# ATmega128RFA1-DevBoard.net
KiCad netlist of a schematic drawn in EAGLE
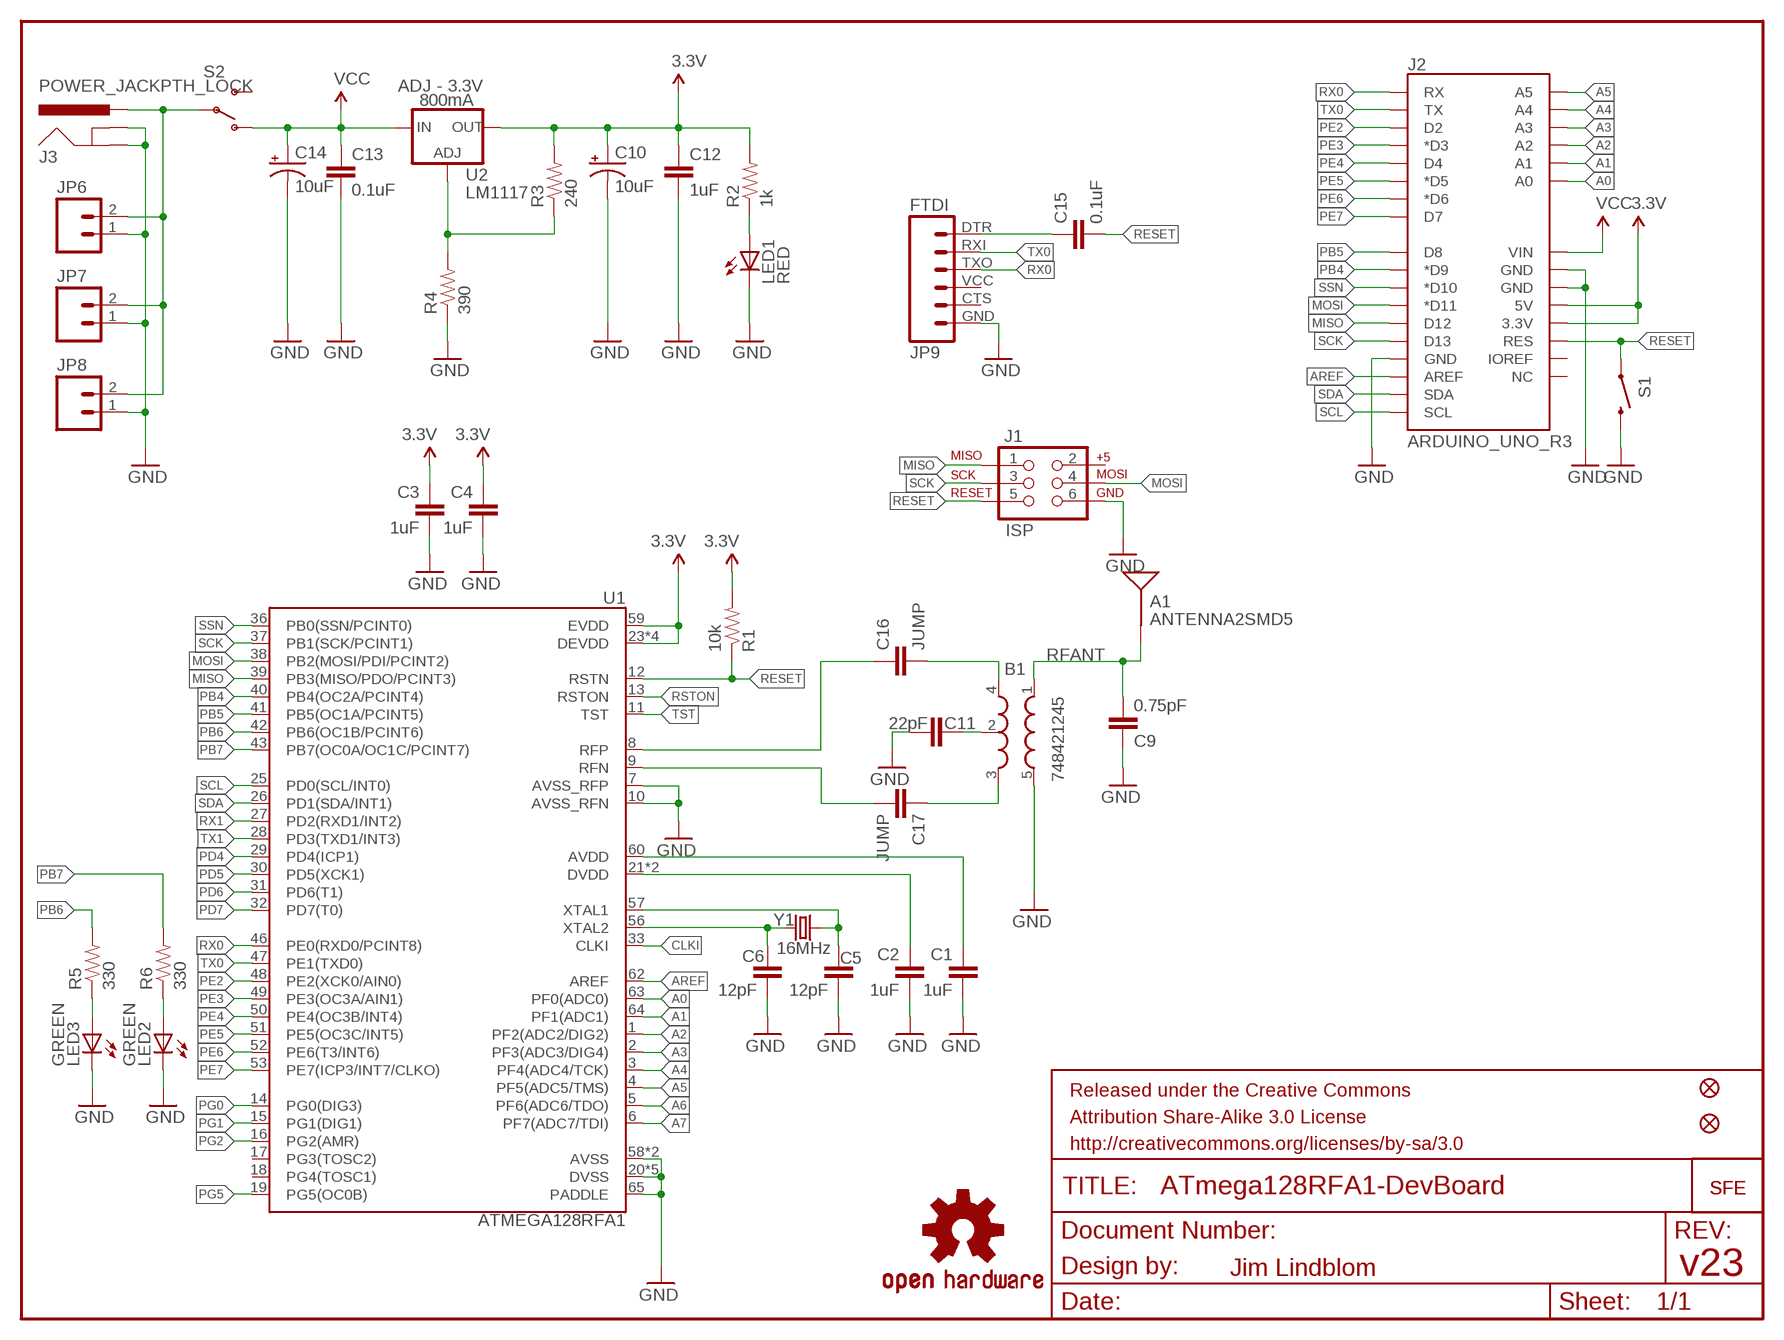
[diagram p0: schematic, sheet 1]

(export (version "E")
  (design (tool "Eeschema 10.0.6"))
  (components
    (comp (ref "A1")
      (value "ANTENNA2SMD5")
      (footprint "eagle-import:ANTENNA-CHIP5")
      (libsource (lib "eagle-import") (part "ANTENNA2SMD5"))
    )
    (comp (ref "B1")
      (value "748421245")
      (footprint "eagle-import:BALUN")
      (libsource (lib "eagle-import") (part "BALUN0805"))
    )
    (comp (ref "C1")
      (value "1uF")
      (footprint "eagle-import:0402-CAP")
      (libsource (lib "eagle-import") (part "SparkFun-Passives_CAP0402-CAP"))
    )
    (comp (ref "C2")
      (value "1uF")
      (footprint "eagle-import:0402-CAP")
      (libsource (lib "eagle-import") (part "SparkFun-Passives_CAP0402-CAP"))
    )
    (comp (ref "C3")
      (value "1uF")
      (footprint "eagle-import:0402-CAP")
      (libsource (lib "eagle-import") (part "SparkFun-Passives_CAP0402-CAP"))
    )
    (comp (ref "C4")
      (value "1uF")
      (footprint "eagle-import:0402-CAP")
      (libsource (lib "eagle-import") (part "SparkFun-Passives_CAP0402-CAP"))
    )
    (comp (ref "C5")
      (value "12pF")
      (footprint "eagle-import:0402-CAP")
      (libsource (lib "eagle-import") (part "SparkFun-Passives_CAP0402-CAP"))
    )
    (comp (ref "C6")
      (value "12pF")
      (footprint "eagle-import:0402-CAP")
      (libsource (lib "eagle-import") (part "SparkFun-Passives_CAP0402-CAP"))
    )
    (comp (ref "C9")
      (value "0.75pF")
      (footprint "eagle-import:0402-CAP")
      (libsource (lib "eagle-import") (part "SparkFun-Passives_CAP0402-CAP"))
    )
    (comp (ref "C10")
      (value "10uF")
      (footprint "eagle-import:EIA3216")
      (libsource (lib "eagle-import") (part "CAP_POL1206"))
    )
    (comp (ref "C11")
      (value "22pF")
      (footprint "eagle-import:0402-CAP")
      (libsource (lib "eagle-import") (part "SparkFun-Passives_CAP0402-CAP"))
    )
    (comp (ref "C12")
      (value "1uF")
      (footprint "eagle-import:0402-CAP")
      (libsource (lib "eagle-import") (part "SparkFun-Passives_CAP0402-CAP"))
    )
    (comp (ref "C13")
      (value "0.1uF")
      (footprint "eagle-import:0402-CAP")
      (libsource (lib "eagle-import") (part "SparkFun-Passives_CAP0402-CAP"))
    )
    (comp (ref "C14")
      (value "10uF")
      (footprint "eagle-import:EIA3216")
      (libsource (lib "eagle-import") (part "CAP_POL1206"))
    )
    (comp (ref "C15")
      (value "0.1uF")
      (footprint "eagle-import:0402-CAP")
      (libsource (lib "eagle-import") (part "SparkFun-Passives_CAP0402-CAP"))
    )
    (comp (ref "C16")
      (value "JUMP")
      (footprint "eagle-import:0402-CAP")
      (libsource (lib "eagle-import") (part "CAP0402-CAP"))
    )
    (comp (ref "C17")
      (value "JUMP")
      (footprint "eagle-import:0402-CAP")
      (libsource (lib "eagle-import") (part "CAP0402-CAP"))
    )
    (comp (ref "FID1")
      (value "FIDUCIALUFIDUCIAL")
      (footprint "eagle-import:MICRO-FIDUCIAL")
      (libsource (lib "eagle-import") (part "FIDUCIALUFIDUCIAL"))
    )
    (comp (ref "FID2")
      (value "FIDUCIALUFIDUCIAL")
      (footprint "eagle-import:MICRO-FIDUCIAL")
      (libsource (lib "eagle-import") (part "FIDUCIALUFIDUCIAL"))
    )
    (comp (ref "J1")
      (value "ISP")
      (footprint "eagle-import:2X3-NS")
      (libsource (lib "eagle-import") (part "AVR_SPI_PRG_6NS"))
    )
    (comp (ref "J2")
      (value "ARDUINO_UNO_R3")
      (footprint "eagle-import:ARDUINO_UNO_R3")
      (libsource (lib "eagle-import") (part "ARDUINO_UNO_R3"))
    )
    (comp (ref "J3")
      (value "POWER_JACKPTH_LOCK")
      (footprint "eagle-import:POWER_JACK_PTH_LOCK")
      (libsource (lib "eagle-import") (part "POWER_JACKPTH_LOCK"))
    )
    (comp (ref "JP4")
      (value "LOGO-SFENEW")
      (footprint "eagle-import:SFE-NEW-WEBLOGO")
      (libsource (lib "eagle-import") (part "LOGO-SFENEW"))
    )
    (comp (ref "JP6")
      (value "M02JST-PTH-2")
      (footprint "eagle-import:JST-2-PTH")
      (libsource (lib "eagle-import") (part "M02JST-PTH-2"))
    )
    (comp (ref "JP7")
      (value "M021X02_NO_SILK")
      (footprint "eagle-import:1X02_NO_SILK")
      (libsource (lib "eagle-import") (part "M021X02_NO_SILK"))
    )
    (comp (ref "JP8")
      (value "M023.5MM-NO_SILK")
      (footprint "eagle-import:SCREWTERMINAL-3.5MM-2-NS")
      (libsource (lib "eagle-import") (part "M023.5MM-NO_SILK"))
    )
    (comp (ref "JP9")
      (value "FTDI")
      (footprint "eagle-import:FTDI_BASIC")
      (libsource (lib "eagle-import") (part "FTDI_BASICPTH"))
    )
    (comp (ref "JP10")
      (value "LOGO-SFENEW")
      (footprint "eagle-import:SFE-NEW-WEBLOGO")
      (libsource (lib "eagle-import") (part "LOGO-SFENEW"))
    )
    (comp (ref "LED1")
      (value "RED")
      (footprint "eagle-import:LED-0603")
      (libsource (lib "eagle-import") (part "LED0603"))
    )
    (comp (ref "LED2")
      (value "GREEN")
      (footprint "eagle-import:LED-0603")
      (libsource (lib "eagle-import") (part "LED0603"))
    )
    (comp (ref "LED3")
      (value "GREEN")
      (footprint "eagle-import:LED-0603")
      (libsource (lib "eagle-import") (part "LED0603"))
    )
    (comp (ref "R1")
      (value "10k")
      (footprint "eagle-import:0402-RES")
      (libsource (lib "eagle-import") (part "SparkFun-Passives_RESISTOR0402-RES"))
    )
    (comp (ref "R2")
      (value "1k")
      (footprint "eagle-import:0402-RES")
      (libsource (lib "eagle-import") (part "SparkFun-Passives_RESISTOR0402-RES"))
    )
    (comp (ref "R3")
      (value "240")
      (footprint "eagle-import:0402-RES")
      (libsource (lib "eagle-import") (part "RESISTOR0402-RES"))
    )
    (comp (ref "R4")
      (value "390")
      (footprint "eagle-import:0402-RES")
      (libsource (lib "eagle-import") (part "RESISTOR0402-RES"))
    )
    (comp (ref "R5")
      (value "330")
      (footprint "eagle-import:0402-RES")
      (libsource (lib "eagle-import") (part "RESISTOR0402-RES"))
    )
    (comp (ref "R6")
      (value "330")
      (footprint "eagle-import:0402-RES")
      (libsource (lib "eagle-import") (part "RESISTOR0402-RES"))
    )
    (comp (ref "S1")
      (value "SWITCH-MOMENTARY-2SMD")
      (footprint "eagle-import:TACTILE_SWITCH_SMD")
      (libsource (lib "eagle-import") (part "SWITCH-MOMENTARY-2SMD"))
    )
    (comp (ref "S2")
      (value "SWITCH-SPST-SMD-A")
      (footprint "eagle-import:SWITCH-SPST-SMD-A")
      (libsource (lib "eagle-import") (part "SWITCH-SPST-SMD-A"))
    )
    (comp (ref "U$1")
      (value "OSHW-LOGOS")
      (footprint "eagle-import:OSHW-LOGO-S")
      (libsource (lib "eagle-import") (part "OSHW-LOGOS"))
    )
    (comp (ref "U1")
      (value "ATMEGA128RFA1")
      (footprint "eagle-import:QFN-64")
      (libsource (lib "eagle-import") (part "ATMEGA128RFA1"))
    )
    (comp (ref "U2")
      (value "LM1117")
      (footprint "eagle-import:SOT223")
      (libsource (lib "eagle-import") (part "V_REG_317SMD"))
    )
    (comp (ref "Y1")
      (value "16MHz")
      (footprint "eagle-import:CRYSTAL-SMD-5X3")
      (libsource (lib "eagle-import") (part "CRYSTAL5X3"))
    )
  )
  (nets
    (net (code "1") (name "/RFANT") (class "Default")
      (node (ref "A1") (pin "FEED") (pinfunction "SIGNAL_FEED") (pintype "bidirectional"))
      (node (ref "B1") (pin "1") (pinfunction "IN_1") (pintype "bidirectional"))
      (node (ref "C9") (pin "2") (pinfunction "2_2") (pintype "passive"))
    )
    (net (code "2") (name "3.3V") (class "Default")
      (node (ref "C10") (pin "A") (pinfunction "+_A") (pintype "passive"))
      (node (ref "C12") (pin "1") (pinfunction "1_1") (pintype "passive"))
      (node (ref "C3") (pin "1") (pinfunction "1_1") (pintype "passive"))
      (node (ref "C4") (pin "1") (pinfunction "1_1") (pintype "passive"))
      (node (ref "J2") (pin "3.3V") (pinfunction "3.3V_3.3V") (pintype "bidirectional"))
      (node (ref "J2") (pin "5V") (pinfunction "5V_5V") (pintype "bidirectional"))
      (node (ref "R1") (pin "2") (pinfunction "2_2") (pintype "passive"))
      (node (ref "R2") (pin "2") (pinfunction "2_2") (pintype "passive"))
      (node (ref "R3") (pin "2") (pinfunction "2_2") (pintype "passive"))
      (node (ref "U1") (pin "23") (pinfunction "DEVDD_23") (pintype "bidirectional"))
      (node (ref "U1") (pin "34") (pinfunction "DEVDD_34") (pintype "bidirectional"))
      (node (ref "U1") (pin "44") (pinfunction "DEVDD_44") (pintype "bidirectional"))
      (node (ref "U1") (pin "54") (pinfunction "DEVDD_54") (pintype "bidirectional"))
      (node (ref "U1") (pin "59") (pinfunction "EVDD_59") (pintype "bidirectional"))
      (node (ref "U2") (pin "2") (pinfunction "OUT_2") (pintype "output"))
    )
    (net (code "3") (name "A0") (class "Default")
      (node (ref "J2") (pin "A0") (pinfunction "A0_A0") (pintype "bidirectional"))
      (node (ref "U1") (pin "63") (pinfunction "PF0(ADC0)_63") (pintype "bidirectional"))
    )
    (net (code "4") (name "A1") (class "Default")
      (node (ref "J2") (pin "A1") (pinfunction "A1_A1") (pintype "bidirectional"))
      (node (ref "U1") (pin "64") (pinfunction "PF1(ADC1)_64") (pintype "bidirectional"))
    )
    (net (code "5") (name "A2") (class "Default")
      (node (ref "J2") (pin "A2") (pinfunction "A2_A2") (pintype "bidirectional"))
      (node (ref "U1") (pin "1") (pinfunction "PF2(ADC2/DIG2)_1") (pintype "bidirectional"))
    )
    (net (code "6") (name "A3") (class "Default")
      (node (ref "J2") (pin "A3") (pinfunction "A3_A3") (pintype "bidirectional"))
      (node (ref "U1") (pin "2") (pinfunction "PF3(ADC3/DIG4)_2") (pintype "bidirectional"))
    )
    (net (code "7") (name "A4") (class "Default")
      (node (ref "J2") (pin "A4") (pinfunction "A4_A4") (pintype "bidirectional"))
      (node (ref "U1") (pin "3") (pinfunction "PF4(ADC4/TCK)_3") (pintype "bidirectional"))
    )
    (net (code "8") (name "A5") (class "Default")
      (node (ref "J2") (pin "A5") (pinfunction "A5_A5") (pintype "bidirectional"))
      (node (ref "U1") (pin "4") (pinfunction "PF5(ADC5/TMS)_4") (pintype "bidirectional"))
    )
    (net (code "9") (name "A6") (class "Default")
      (node (ref "U1") (pin "5") (pinfunction "PF6(ADC6/TDO)_5") (pintype "bidirectional"))
    )
    (net (code "10") (name "A7") (class "Default")
      (node (ref "U1") (pin "6") (pinfunction "PF7(ADC7/TDI)_6") (pintype "bidirectional"))
    )
    (net (code "11") (name "AREF") (class "Default")
      (node (ref "J2") (pin "AREF") (pinfunction "AREF_AREF") (pintype "bidirectional"))
      (node (ref "U1") (pin "62") (pinfunction "AREF_62") (pintype "bidirectional"))
    )
    (net (code "12") (name "CLKI") (class "Default")
      (node (ref "U1") (pin "33") (pinfunction "CLKI_33") (pintype "bidirectional"))
    )
    (net (code "13") (name "GND") (class "Default")
      (node (ref "B1") (pin "5") (pinfunction "GND_5") (pintype "bidirectional"))
      (node (ref "C1") (pin "2") (pinfunction "2_2") (pintype "passive"))
      (node (ref "C10") (pin "C") (pinfunction "-_C") (pintype "passive"))
      (node (ref "C11") (pin "2") (pinfunction "2_2") (pintype "passive"))
      (node (ref "C12") (pin "2") (pinfunction "2_2") (pintype "passive"))
      (node (ref "C13") (pin "2") (pinfunction "2_2") (pintype "passive"))
      (node (ref "C14") (pin "C") (pinfunction "-_C") (pintype "passive"))
      (node (ref "C2") (pin "2") (pinfunction "2_2") (pintype "passive"))
      (node (ref "C3") (pin "2") (pinfunction "2_2") (pintype "passive"))
      (node (ref "C4") (pin "2") (pinfunction "2_2") (pintype "passive"))
      (node (ref "C5") (pin "2") (pinfunction "2_2") (pintype "passive"))
      (node (ref "C6") (pin "2") (pinfunction "2_2") (pintype "passive"))
      (node (ref "C9") (pin "1") (pinfunction "1_1") (pintype "passive"))
      (node (ref "J1") (pin "6") (pinfunction "6_6") (pintype "passive"))
      (node (ref "J2") (pin "GND@0") (pinfunction "GND_GND@0") (pintype "bidirectional"))
      (node (ref "J2") (pin "GND@1") (pinfunction "GND_GND@1") (pintype "bidirectional"))
      (node (ref "J2") (pin "GND@2") (pinfunction "GND_GND@2") (pintype "bidirectional"))
      (node (ref "J3") (pin "GND") (pinfunction "GND_GND") (pintype "bidirectional"))
      (node (ref "J3") (pin "GNDBREAK") (pinfunction "GNDBREAK_GNDBREAK") (pintype "bidirectional"))
      (node (ref "JP6") (pin "1") (pinfunction "1_1") (pintype "passive"))
      (node (ref "JP7") (pin "1") (pinfunction "1_1") (pintype "passive"))
      (node (ref "JP8") (pin "1") (pinfunction "1_1") (pintype "passive"))
      (node (ref "JP9") (pin "GND") (pinfunction "6_GND") (pintype "passive"))
      (node (ref "LED1") (pin "C") (pinfunction "C_C") (pintype "passive"))
      (node (ref "LED2") (pin "C") (pinfunction "C_C") (pintype "passive"))
      (node (ref "LED3") (pin "C") (pinfunction "C_C") (pintype "passive"))
      (node (ref "R4") (pin "1") (pinfunction "1_1") (pintype "passive"))
      (node (ref "S1") (pin "3") (pinfunction "2_3") (pintype "passive"))
      (node (ref "U1") (pin "10") (pinfunction "AVSS_RFN_10") (pintype "bidirectional"))
      (node (ref "U1") (pin "20") (pinfunction "DVSS_20") (pintype "bidirectional"))
      (node (ref "U1") (pin "24") (pinfunction "DVSS_24") (pintype "bidirectional"))
      (node (ref "U1") (pin "35") (pinfunction "DVSS_35") (pintype "bidirectional"))
      (node (ref "U1") (pin "45") (pinfunction "DVSS_45") (pintype "bidirectional"))
      (node (ref "U1") (pin "55") (pinfunction "DVSS_55") (pintype "bidirectional"))
      (node (ref "U1") (pin "58") (pinfunction "AVSS_58") (pintype "bidirectional"))
      (node (ref "U1") (pin "61") (pinfunction "AVSS_61") (pintype "bidirectional"))
      (node (ref "U1") (pin "65") (pinfunction "PADDLE_65") (pintype "bidirectional"))
      (node (ref "U1") (pin "7") (pinfunction "AVSS_RFP_7") (pintype "bidirectional"))
    )
    (net (code "14") (name "MISO") (class "Default")
      (node (ref "J1") (pin "1") (pinfunction "1_1") (pintype "passive"))
      (node (ref "J2") (pin "D12") (pinfunction "D12_D12") (pintype "bidirectional"))
      (node (ref "U1") (pin "39") (pinfunction "PB3(MISO/PDO/PCINT3)_39") (pintype "bidirectional"))
    )
    (net (code "15") (name "MOSI") (class "Default")
      (node (ref "J1") (pin "4") (pinfunction "4_4") (pintype "passive"))
      (node (ref "J2") (pin "D11") (pinfunction "*D11_D11") (pintype "bidirectional"))
      (node (ref "U1") (pin "38") (pinfunction "PB2(MOSI/PDI/PCINT2)_38") (pintype "bidirectional"))
    )
    (net (code "16") (name "Net-(B1-GND-Pad2)") (class "Default")
      (node (ref "B1") (pin "2") (pinfunction "GND_2") (pintype "bidirectional"))
      (node (ref "C11") (pin "1") (pinfunction "1_1") (pintype "passive"))
    )
    (net (code "17") (name "Net-(B1-OUT1)") (class "Default")
      (node (ref "B1") (pin "4") (pinfunction "OUT1_4") (pintype "bidirectional"))
      (node (ref "C16") (pin "2") (pinfunction "2_2") (pintype "passive"))
    )
    (net (code "18") (name "Net-(B1-OUT2)") (class "Default")
      (node (ref "B1") (pin "3") (pinfunction "OUT2_3") (pintype "bidirectional"))
      (node (ref "C17") (pin "1") (pinfunction "1_1") (pintype "passive"))
    )
    (net (code "19") (name "Net-(C2-Pad1)") (class "Default")
      (node (ref "C2") (pin "1") (pinfunction "1_1") (pintype "passive"))
      (node (ref "U1") (pin "21") (pinfunction "DVDD_21") (pintype "bidirectional"))
      (node (ref "U1") (pin "22") (pinfunction "DVDD_22") (pintype "bidirectional"))
    )
    (net (code "20") (name "Net-(JP9-1)") (class "Default")
      (node (ref "C15") (pin "1") (pinfunction "1_1") (pintype "passive"))
      (node (ref "JP9") (pin "DTR") (pinfunction "1_DTR") (pintype "passive"))
    )
    (net (code "21") (name "Net-(LED1-PadA)") (class "Default")
      (node (ref "LED1") (pin "A") (pinfunction "A_A") (pintype "passive"))
      (node (ref "R2") (pin "1") (pinfunction "1_1") (pintype "passive"))
    )
    (net (code "22") (name "Net-(LED2-PadA)") (class "Default")
      (node (ref "LED2") (pin "A") (pinfunction "A_A") (pintype "passive"))
      (node (ref "R6") (pin "1") (pinfunction "1_1") (pintype "passive"))
    )
    (net (code "23") (name "Net-(LED3-PadA)") (class "Default")
      (node (ref "LED3") (pin "A") (pinfunction "A_A") (pintype "passive"))
      (node (ref "R5") (pin "1") (pinfunction "1_1") (pintype "passive"))
    )
    (net (code "24") (name "Net-(S2-P)") (class "Default")
      (node (ref "J3") (pin "PWR") (pinfunction "PWR_PWR") (pintype "bidirectional"))
      (node (ref "JP6") (pin "2") (pinfunction "2_2") (pintype "passive"))
      (node (ref "JP7") (pin "2") (pinfunction "2_2") (pintype "passive"))
      (node (ref "JP8") (pin "2") (pinfunction "2_2") (pintype "passive"))
      (node (ref "S2") (pin "2") (pinfunction "P_2") (pintype "passive"))
    )
    (net (code "25") (name "Net-(U1-AVDD)") (class "Default")
      (node (ref "C1") (pin "1") (pinfunction "1_1") (pintype "passive"))
      (node (ref "U1") (pin "60") (pinfunction "AVDD_60") (pintype "bidirectional"))
    )
    (net (code "26") (name "Net-(U1-RFN)") (class "Default")
      (node (ref "C17") (pin "2") (pinfunction "2_2") (pintype "passive"))
      (node (ref "U1") (pin "9") (pinfunction "RFN_9") (pintype "bidirectional"))
    )
    (net (code "27") (name "Net-(U1-RFP)") (class "Default")
      (node (ref "C16") (pin "1") (pinfunction "1_1") (pintype "passive"))
      (node (ref "U1") (pin "8") (pinfunction "RFP_8") (pintype "bidirectional"))
    )
    (net (code "28") (name "Net-(U1-XTAL1)") (class "Default")
      (node (ref "C5") (pin "1") (pinfunction "1_1") (pintype "passive"))
      (node (ref "U1") (pin "57") (pinfunction "XTAL1_57") (pintype "bidirectional"))
      (node (ref "Y1") (pin "3") (pinfunction "2_3") (pintype "passive"))
    )
    (net (code "29") (name "Net-(U1-XTAL2)") (class "Default")
      (node (ref "C6") (pin "1") (pinfunction "1_1") (pintype "passive"))
      (node (ref "U1") (pin "56") (pinfunction "XTAL2_56") (pintype "bidirectional"))
      (node (ref "Y1") (pin "1") (pinfunction "1_1") (pintype "passive"))
    )
    (net (code "30") (name "Net-(U2-ADJ)") (class "Default")
      (node (ref "R3") (pin "1") (pinfunction "1_1") (pintype "passive"))
      (node (ref "R4") (pin "2") (pinfunction "2_2") (pintype "passive"))
      (node (ref "U2") (pin "1") (pinfunction "ADJ_1") (pintype "input"))
    )
    (net (code "31") (name "PB4") (class "Default")
      (node (ref "J2") (pin "D9") (pinfunction "*D9_D9") (pintype "bidirectional"))
      (node (ref "U1") (pin "40") (pinfunction "PB4(OC2A/PCINT4)_40") (pintype "bidirectional"))
    )
    (net (code "32") (name "PB5") (class "Default")
      (node (ref "J2") (pin "D8") (pinfunction "D8_D8") (pintype "bidirectional"))
      (node (ref "U1") (pin "41") (pinfunction "PB5(OC1A/PCINT5)_41") (pintype "bidirectional"))
    )
    (net (code "33") (name "PB6") (class "Default")
      (node (ref "R5") (pin "2") (pinfunction "2_2") (pintype "passive"))
      (node (ref "U1") (pin "42") (pinfunction "PB6(OC1B/PCINT6)_42") (pintype "bidirectional"))
    )
    (net (code "34") (name "PB7") (class "Default")
      (node (ref "R6") (pin "2") (pinfunction "2_2") (pintype "passive"))
      (node (ref "U1") (pin "43") (pinfunction "PB7(OC0A/OC1C/PCINT7)_43") (pintype "bidirectional"))
    )
    (net (code "35") (name "PD4") (class "Default")
      (node (ref "U1") (pin "29") (pinfunction "PD4(ICP1)_29") (pintype "bidirectional"))
    )
    (net (code "36") (name "PD5") (class "Default")
      (node (ref "U1") (pin "30") (pinfunction "PD5(XCK1)_30") (pintype "bidirectional"))
    )
    (net (code "37") (name "PD6") (class "Default")
      (node (ref "U1") (pin "31") (pinfunction "PD6(T1)_31") (pintype "bidirectional"))
    )
    (net (code "38") (name "PD7") (class "Default")
      (node (ref "U1") (pin "32") (pinfunction "PD7(T0)_32") (pintype "bidirectional"))
    )
    (net (code "39") (name "PE2") (class "Default")
      (node (ref "J2") (pin "D2") (pinfunction "D2_D2") (pintype "bidirectional"))
      (node (ref "U1") (pin "48") (pinfunction "PE2(XCK0/AIN0)_48") (pintype "bidirectional"))
    )
    (net (code "40") (name "PE3") (class "Default")
      (node (ref "J2") (pin "D3") (pinfunction "*D3_D3") (pintype "bidirectional"))
      (node (ref "U1") (pin "49") (pinfunction "PE3(OC3A/AIN1)_49") (pintype "bidirectional"))
    )
    (net (code "41") (name "PE4") (class "Default")
      (node (ref "J2") (pin "D4") (pinfunction "D4_D4") (pintype "bidirectional"))
      (node (ref "U1") (pin "50") (pinfunction "PE4(OC3B/INT4)_50") (pintype "bidirectional"))
    )
    (net (code "42") (name "PE5") (class "Default")
      (node (ref "J2") (pin "D5") (pinfunction "*D5_D5") (pintype "bidirectional"))
      (node (ref "U1") (pin "51") (pinfunction "PE5(OC3C/INT5)_51") (pintype "bidirectional"))
    )
    (net (code "43") (name "PE6") (class "Default")
      (node (ref "J2") (pin "D6") (pinfunction "*D6_D6") (pintype "bidirectional"))
      (node (ref "U1") (pin "52") (pinfunction "PE6(T3/INT6)_52") (pintype "bidirectional"))
    )
    (net (code "44") (name "PE7") (class "Default")
      (node (ref "J2") (pin "D7") (pinfunction "D7_D7") (pintype "bidirectional"))
      (node (ref "U1") (pin "53") (pinfunction "PE7(ICP3/INT7/CLKO)_53") (pintype "bidirectional"))
    )
    (net (code "45") (name "PG0") (class "Default")
      (node (ref "U1") (pin "14") (pinfunction "PG0(DIG3)_14") (pintype "bidirectional"))
    )
    (net (code "46") (name "PG1") (class "Default")
      (node (ref "U1") (pin "15") (pinfunction "PG1(DIG1)_15") (pintype "bidirectional"))
    )
    (net (code "47") (name "PG2") (class "Default")
      (node (ref "U1") (pin "16") (pinfunction "PG2(AMR)_16") (pintype "bidirectional"))
    )
    (net (code "48") (name "PG5") (class "Default")
      (node (ref "U1") (pin "19") (pinfunction "PG5(OC0B)_19") (pintype "bidirectional"))
    )
    (net (code "49") (name "RESET") (class "Default")
      (node (ref "C15") (pin "2") (pinfunction "2_2") (pintype "passive"))
      (node (ref "J1") (pin "5") (pinfunction "5_5") (pintype "passive"))
      (node (ref "J2") (pin "RES") (pinfunction "RES_RES") (pintype "bidirectional"))
      (node (ref "R1") (pin "1") (pinfunction "1_1") (pintype "passive"))
      (node (ref "S1") (pin "1") (pinfunction "1_1") (pintype "passive"))
      (node (ref "U1") (pin "12") (pinfunction "RSTN_12") (pintype "bidirectional"))
    )
    (net (code "50") (name "RSTON") (class "Default")
      (node (ref "U1") (pin "13") (pinfunction "RSTON_13") (pintype "bidirectional"))
    )
    (net (code "51") (name "RX0") (class "Default")
      (node (ref "J2") (pin "RX") (pinfunction "RX_RX") (pintype "bidirectional"))
      (node (ref "JP9") (pin "TXO") (pinfunction "3_TXO") (pintype "passive"))
      (node (ref "U1") (pin "46") (pinfunction "PE0(RXD0/PCINT8)_46") (pintype "bidirectional"))
    )
    (net (code "52") (name "RX1") (class "Default")
      (node (ref "U1") (pin "27") (pinfunction "PD2(RXD1/INT2)_27") (pintype "bidirectional"))
    )
    (net (code "53") (name "SCK") (class "Default")
      (node (ref "J1") (pin "3") (pinfunction "3_3") (pintype "passive"))
      (node (ref "J2") (pin "D13") (pinfunction "D13_D13") (pintype "bidirectional"))
      (node (ref "U1") (pin "37") (pinfunction "PB1(SCK/PCINT1)_37") (pintype "bidirectional"))
    )
    (net (code "54") (name "SCL") (class "Default")
      (node (ref "J2") (pin "SCL") (pinfunction "SCL_SCL") (pintype "bidirectional"))
      (node (ref "U1") (pin "25") (pinfunction "PD0(SCL/INT0)_25") (pintype "bidirectional"))
    )
    (net (code "55") (name "SDA") (class "Default")
      (node (ref "J2") (pin "SDA") (pinfunction "SDA_SDA") (pintype "bidirectional"))
      (node (ref "U1") (pin "26") (pinfunction "PD1(SDA/INT1)_26") (pintype "bidirectional"))
    )
    (net (code "56") (name "SSN") (class "Default")
      (node (ref "J2") (pin "D10") (pinfunction "*D10_D10") (pintype "bidirectional"))
      (node (ref "U1") (pin "36") (pinfunction "PB0(SSN/PCINT0)_36") (pintype "bidirectional"))
    )
    (net (code "57") (name "TST") (class "Default")
      (node (ref "U1") (pin "11") (pinfunction "TST_11") (pintype "bidirectional"))
    )
    (net (code "58") (name "TX0") (class "Default")
      (node (ref "J2") (pin "TX") (pinfunction "TX_TX") (pintype "bidirectional"))
      (node (ref "JP9") (pin "RXI") (pinfunction "2_RXI") (pintype "passive"))
      (node (ref "U1") (pin "47") (pinfunction "PE1(TXD0)_47") (pintype "bidirectional"))
    )
    (net (code "59") (name "TX1") (class "Default")
      (node (ref "U1") (pin "28") (pinfunction "PD3(TXD1/INT3)_28") (pintype "bidirectional"))
    )
    (net (code "60") (name "VCC") (class "Default")
      (node (ref "C13") (pin "1") (pinfunction "1_1") (pintype "passive"))
      (node (ref "C14") (pin "A") (pinfunction "+_A") (pintype "passive"))
      (node (ref "J2") (pin "VIN") (pinfunction "VIN_VIN") (pintype "bidirectional"))
      (node (ref "S2") (pin "1") (pinfunction "O_1") (pintype "passive"))
      (node (ref "U2") (pin "3") (pinfunction "IN_3") (pintype "input"))
    )
    (net (code "61") (name "unconnected-(J1-Pad2)") (class "Default")
      (node (ref "J1") (pin "2") (pinfunction "2_2") (pintype "passive"))
    )
    (net (code "62") (name "unconnected-(J2-PadIOREF)") (class "Default")
      (node (ref "J2") (pin "IOREF") (pinfunction "IOREF_IOREF") (pintype "bidirectional"))
    )
    (net (code "63") (name "unconnected-(J2-PadNC)") (class "Default")
      (node (ref "J2") (pin "NC") (pinfunction "NC_NC") (pintype "bidirectional"))
    )
    (net (code "64") (name "unconnected-(JP9-4-PadVCC)") (class "Default")
      (node (ref "JP9") (pin "VCC") (pinfunction "4_VCC") (pintype "passive"))
    )
    (net (code "65") (name "unconnected-(JP9-5-PadCTS)") (class "Default")
      (node (ref "JP9") (pin "CTS") (pinfunction "5_CTS") (pintype "passive"))
    )
    (net (code "66") (name "unconnected-(S2-S-Pad3)") (class "Default")
      (node (ref "S2") (pin "3") (pinfunction "S_3") (pintype "passive"))
    )
    (net (code "67") (name "unconnected-(U1-PG3(TOSC2)-Pad17)") (class "Default")
      (node (ref "U1") (pin "17") (pinfunction "PG3(TOSC2)_17") (pintype "bidirectional"))
    )
    (net (code "68") (name "unconnected-(U1-PG4(TOSC1)-Pad18)") (class "Default")
      (node (ref "U1") (pin "18") (pinfunction "PG4(TOSC1)_18") (pintype "bidirectional"))
    )
  )
)
